# usb.net
KiCad netlist of a schematic drawn in EAGLE
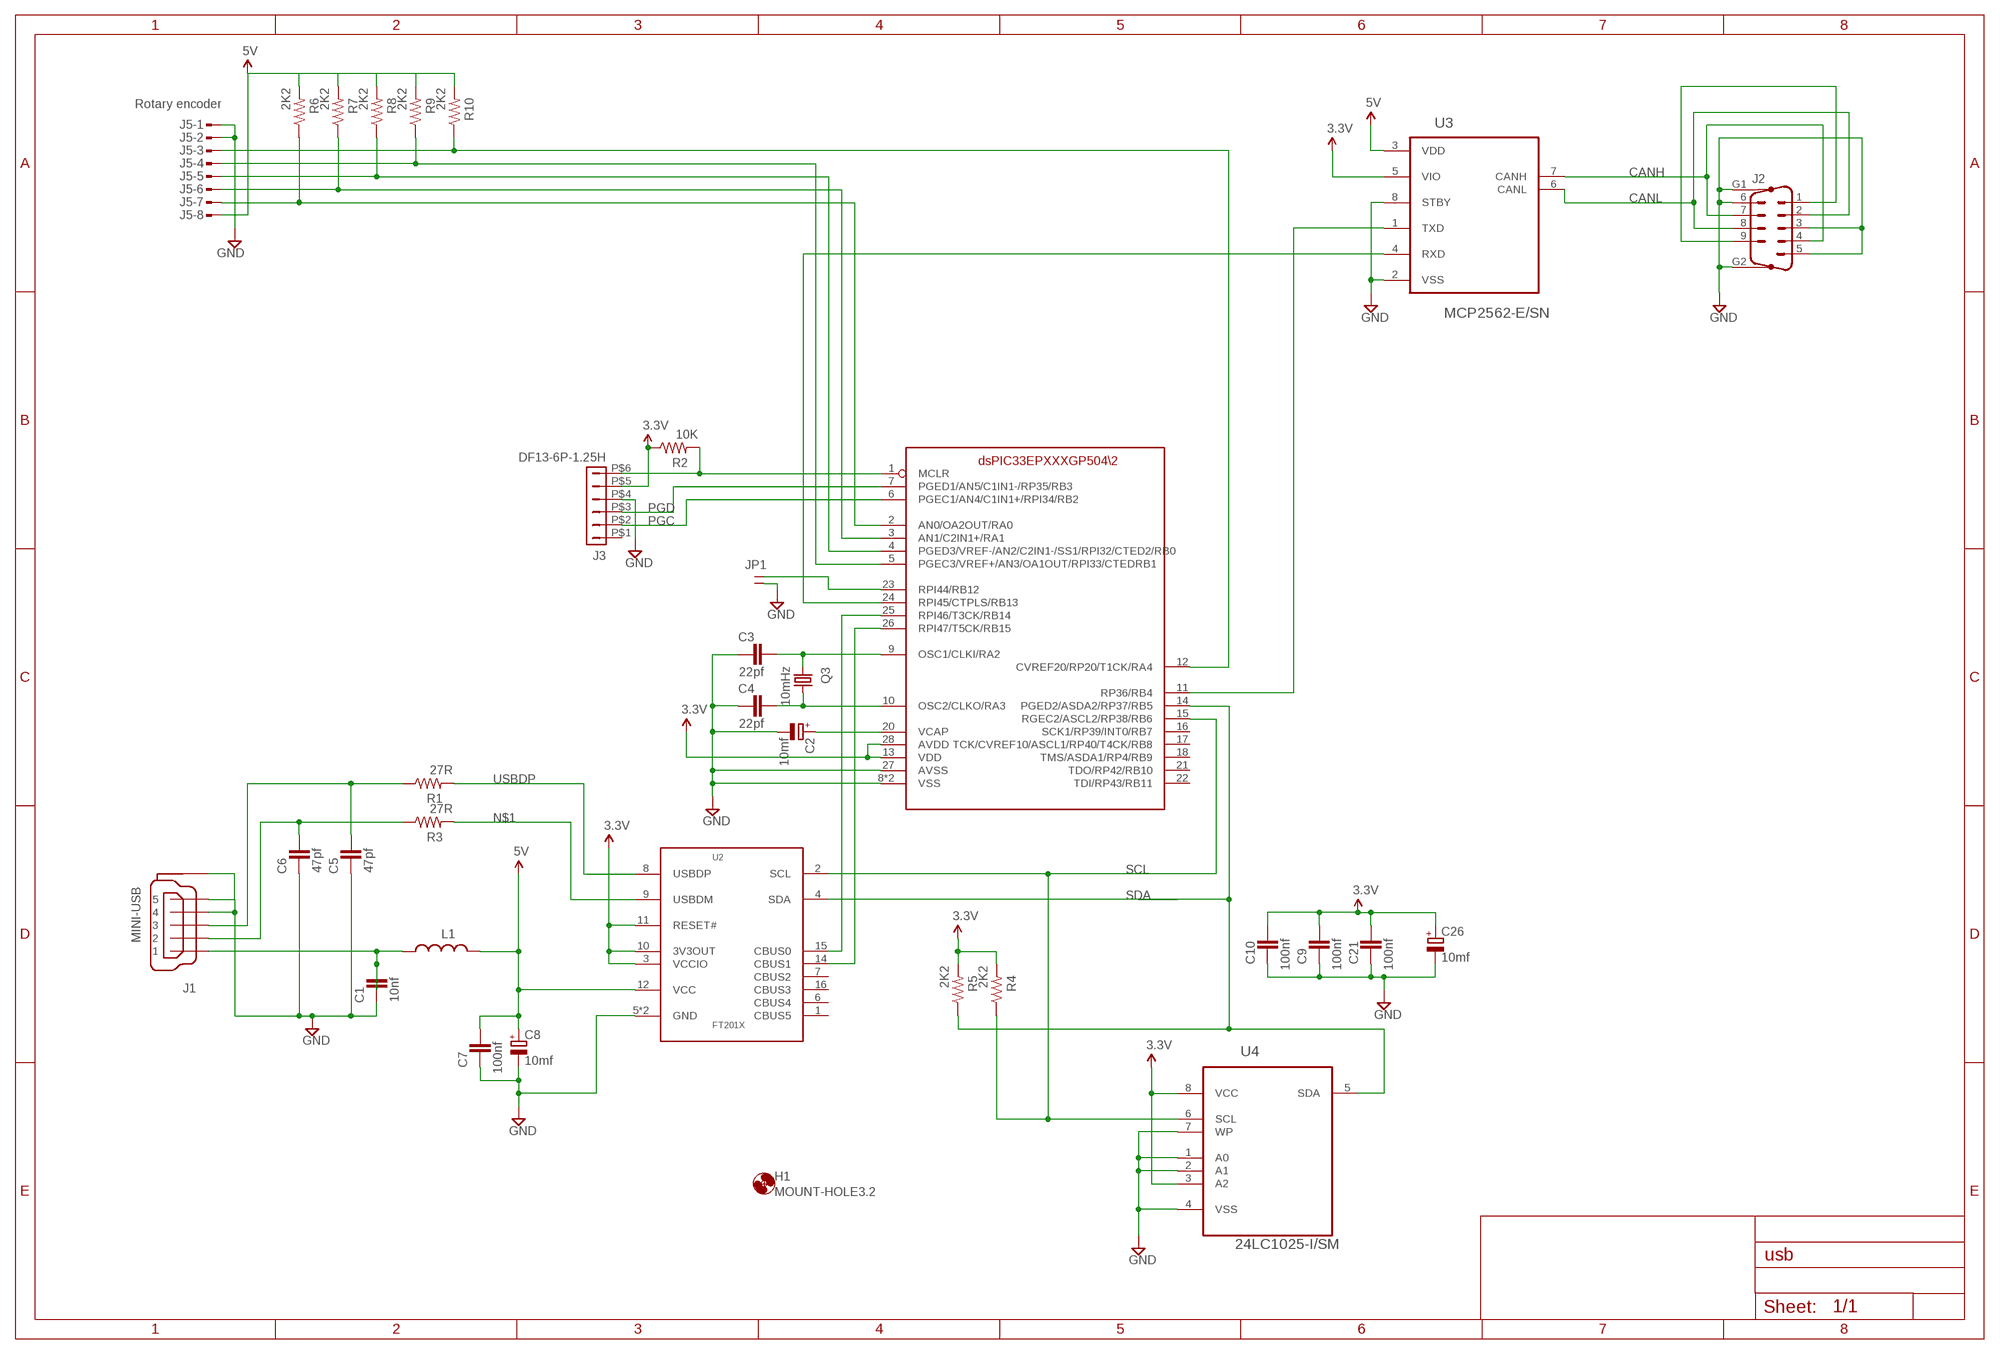
[diagram p0: schematic, sheet 1]

(export (version "E")
  (design (tool "Eeschema 10.0.6"))
  (components
    (comp (ref "C1")
      (value "10nf")
      (footprint "eagle-import:C805")
      (libsource (lib "eagle-import") (part "CAPACITOR_NPOL-0805"))
    )
    (comp (ref "C2")
      (value "10mf")
      (footprint "eagle-import:SMC_A")
      (libsource (lib "eagle-import") (part "CAPACITOR_POL-SMC_A"))
    )
    (comp (ref "C3")
      (value "22pf")
      (footprint "eagle-import:C805")
      (libsource (lib "eagle-import") (part "CAPACITOR_NPOL-0805"))
    )
    (comp (ref "C4")
      (value "22pf")
      (footprint "eagle-import:C805")
      (libsource (lib "eagle-import") (part "CAPACITOR_NPOL-0805"))
    )
    (comp (ref "C5")
      (value "47pf")
      (footprint "eagle-import:C805")
      (libsource (lib "eagle-import") (part "CAPACITOR_NPOL-0805"))
    )
    (comp (ref "C6")
      (value "47pf")
      (footprint "eagle-import:C805")
      (libsource (lib "eagle-import") (part "CAPACITOR_NPOL-0805"))
    )
    (comp (ref "C7")
      (value "100nf")
      (footprint "eagle-import:C805")
      (libsource (lib "eagle-import") (part "CAPACITOR_NPOL-0805"))
    )
    (comp (ref "C8")
      (value "10mf")
      (footprint "eagle-import:SMC_A")
      (libsource (lib "eagle-import") (part "CAPACITOR_POL-SMC_A"))
    )
    (comp (ref "C9")
      (value "100nf")
      (footprint "eagle-import:C805")
      (libsource (lib "eagle-import") (part "CAPACITOR_NPOL-0805"))
    )
    (comp (ref "C10")
      (value "100nf")
      (footprint "eagle-import:C805")
      (libsource (lib "eagle-import") (part "CAPACITOR_NPOL-0805"))
    )
    (comp (ref "C21")
      (value "100nf")
      (footprint "eagle-import:C805")
      (libsource (lib "eagle-import") (part "CAPACITOR_NPOL-0805"))
    )
    (comp (ref "C26")
      (value "10mf")
      (footprint "eagle-import:SMC_A")
      (libsource (lib "eagle-import") (part "CAPACITOR_POL-SMC_A"))
    )
    (comp (ref "H1")
      (value "MOUNT-HOLE3.2")
      (footprint "eagle-import:3,2")
      (libsource (lib "eagle-import") (part "MOUNT-HOLE3.2"))
    )
    (comp (ref "J1")
      (value "MINI-USB")
      (footprint "eagle-import:MINI-USB")
      (libsource (lib "eagle-import") (part "MINI-USB"))
    )
    (comp (ref "J2")
      (value "M09HP")
      (footprint "eagle-import:M09HP")
      (libsource (lib "eagle-import") (part "M09HP"))
    )
    (comp (ref "J3")
      (value "DF13-6P-1.25H")
      (footprint "eagle-import:DF13A-6P-1.25H")
      (libsource (lib "eagle-import") (part "DF13-6P-1.25H"))
    )
    (comp (ref "J5")
      (value "MTOP-8")
      (footprint "eagle-import:MTOP-8")
      (fields (field (name "PARTNO") "7-215079-8"))
      (libsource (lib "eagle-import") (part "MTOP-8"))
    )
    (comp (ref "JP1")
      (value "JUMPER-1X2")
      (footprint "eagle-import:JUMPER-1X2")
      (libsource (lib "eagle-import") (part "JUMPER-1X2"))
    )
    (comp (ref "L1")
      (value "FERRITE-0603")
      (footprint "eagle-import:FB603")
      (libsource (lib "eagle-import") (part "FERRITE-0603"))
    )
    (comp (ref "Q3")
      (value "10mHz")
      (footprint "eagle-import:HC49_S")
      (fields (field (name "PARTNO") "9B-10.000MBBK-B"))
      (libsource (lib "eagle-import") (part "CRYSTALHC49S"))
    )
    (comp (ref "R1")
      (value "27R")
      (footprint "eagle-import:0603-RES")
      (fields (field (name "PARTNO") "ERJ-3GEYJ103V"))
      (libsource (lib "eagle-import") (part "RESISTOR0603-RES"))
    )
    (comp (ref "R2")
      (value "10K")
      (footprint "eagle-import:0603-RES")
      (fields (field (name "PARTNO") "ERJ-3GEYJ103V"))
      (libsource (lib "eagle-import") (part "RESISTOR0603-RES"))
    )
    (comp (ref "R3")
      (value "27R")
      (footprint "eagle-import:0603-RES")
      (fields (field (name "PARTNO") "ERJ-3GEYJ103V"))
      (libsource (lib "eagle-import") (part "RESISTOR0603-RES"))
    )
    (comp (ref "R4")
      (value "2K2")
      (footprint "eagle-import:0603-RES")
      (fields (field (name "PARTNO") "ERJ-3GEYJ103V"))
      (libsource (lib "eagle-import") (part "RESISTOR0603-RES"))
    )
    (comp (ref "R5")
      (value "2K2")
      (footprint "eagle-import:0603-RES")
      (fields (field (name "PARTNO") "ERJ-3GEYJ103V"))
      (libsource (lib "eagle-import") (part "RESISTOR0603-RES"))
    )
    (comp (ref "R6")
      (value "2K2")
      (footprint "eagle-import:0603-RES")
      (fields (field (name "PARTNO") "RC0603FR-072K2L"))
      (libsource (lib "eagle-import") (part "RESISTOR0603-RES"))
    )
    (comp (ref "R7")
      (value "2K2")
      (footprint "eagle-import:0603-RES")
      (fields (field (name "PARTNO") "RC0603FR-072K2L"))
      (libsource (lib "eagle-import") (part "RESISTOR0603-RES"))
    )
    (comp (ref "R8")
      (value "2K2")
      (footprint "eagle-import:0603-RES")
      (fields (field (name "PARTNO") "RC0603FR-072K2L"))
      (libsource (lib "eagle-import") (part "RESISTOR0603-RES"))
    )
    (comp (ref "R9")
      (value "2K2")
      (footprint "eagle-import:0603-RES")
      (fields (field (name "PARTNO") "RC0603FR-072K2L"))
      (libsource (lib "eagle-import") (part "RESISTOR0603-RES"))
    )
    (comp (ref "R10")
      (value "2K2")
      (footprint "eagle-import:0603-RES")
      (fields (field (name "PARTNO") "RC0603FR-072K2L"))
      (libsource (lib "eagle-import") (part "RESISTOR0603-RES"))
    )
    (comp (ref "U1")
      (value "DSPIC33EPXXXGP502")
      (footprint "eagle-import:SOIC-28")
      (libsource (lib "eagle-import") (part "DSPIC33EPXXXGP502"))
    )
    (comp (ref "U2")
      (value "FT201X")
      (footprint "eagle-import:TSSOP-16")
      (libsource (lib "eagle-import") (part "FT201X"))
    )
    (comp (ref "U3")
      (value "MCP2562-E/SN")
      (footprint "eagle-import:SOIC-8N")
      (libsource (lib "eagle-import") (part "MCP2562-E/SN"))
    )
    (comp (ref "U4")
      (value "24LC1025-I/SM")
      (footprint "eagle-import:SOIC8-N_MC")
      (libsource (lib "eagle-import") (part "24LC1025-I/SM"))
    )
  )
  (nets
    (net (code "1") (name "/CANH") (class "Default")
      (node (ref "J2") (pin "4") (pinfunction "4_4") (pintype "passive"))
      (node (ref "J2") (pin "7") (pinfunction "7_7") (pintype "passive"))
      (node (ref "U3") (pin "7") (pinfunction "CANH_7") (pintype "bidirectional"))
    )
    (net (code "2") (name "/CANL") (class "Default")
      (node (ref "J2") (pin "2") (pinfunction "2_2") (pintype "passive"))
      (node (ref "J2") (pin "8") (pinfunction "8_8") (pintype "passive"))
      (node (ref "U3") (pin "6") (pinfunction "CANL_6") (pintype "bidirectional"))
    )
    (net (code "3") (name "/N$1") (class "Default")
      (node (ref "R3") (pin "2") (pinfunction "2_2") (pintype "passive"))
      (node (ref "U2") (pin "9") (pinfunction "USBDM_9") (pintype "bidirectional"))
    )
    (net (code "4") (name "/PGC") (class "Default")
      (node (ref "J3") (pin "P$2") (pinfunction "2_P$2") (pintype "passive"))
      (node (ref "U1") (pin "6") (pinfunction "PGEC1/AN4/C1IN1+/RPI34/RB2_6") (pintype "bidirectional"))
    )
    (net (code "5") (name "/PGD") (class "Default")
      (node (ref "J3") (pin "P$3") (pinfunction "3_P$3") (pintype "passive"))
      (node (ref "U1") (pin "7") (pinfunction "PGED1/AN5/C1IN1-/RP35/RB3_7") (pintype "bidirectional"))
    )
    (net (code "6") (name "/SCL") (class "Default")
      (node (ref "R4") (pin "1") (pinfunction "1_1") (pintype "passive"))
      (node (ref "U1") (pin "15") (pinfunction "RGEC2/ASCL2/RP38/RB6_15") (pintype "bidirectional"))
      (node (ref "U2") (pin "2") (pinfunction "SCL_2") (pintype "bidirectional"))
      (node (ref "U4") (pin "6") (pinfunction "SCL_6") (pintype "input"))
    )
    (net (code "7") (name "/SDA") (class "Default")
      (node (ref "R5") (pin "1") (pinfunction "1_1") (pintype "passive"))
      (node (ref "U1") (pin "14") (pinfunction "PGED2/ASDA2/RP37/RB5_14") (pintype "bidirectional"))
      (node (ref "U2") (pin "4") (pinfunction "SDA_4") (pintype "bidirectional"))
      (node (ref "U4") (pin "5") (pinfunction "SDA_5") (pintype "bidirectional"))
    )
    (net (code "8") (name "/USBDP") (class "Default")
      (node (ref "R1") (pin "2") (pinfunction "2_2") (pintype "passive"))
      (node (ref "U2") (pin "8") (pinfunction "USBDP_8") (pintype "bidirectional"))
    )
    (net (code "9") (name "3.3V") (class "Default")
      (node (ref "C10") (pin "1") (pinfunction "1_1") (pintype "passive"))
      (node (ref "C21") (pin "1") (pinfunction "1_1") (pintype "passive"))
      (node (ref "C26") (pin "+") (pinfunction "+_+") (pintype "passive"))
      (node (ref "C9") (pin "1") (pinfunction "1_1") (pintype "passive"))
      (node (ref "J3") (pin "P$5") (pinfunction "5_P$5") (pintype "passive"))
      (node (ref "R2") (pin "1") (pinfunction "1_1") (pintype "passive"))
      (node (ref "R4") (pin "2") (pinfunction "2_2") (pintype "passive"))
      (node (ref "R5") (pin "2") (pinfunction "2_2") (pintype "passive"))
      (node (ref "U1") (pin "13") (pinfunction "VDD_13") (pintype "bidirectional"))
      (node (ref "U1") (pin "28") (pinfunction "AVDD_28") (pintype "bidirectional"))
      (node (ref "U2") (pin "10") (pinfunction "3V3OUT_10") (pintype "bidirectional"))
      (node (ref "U2") (pin "11") (pinfunction "RESET#_11") (pintype "bidirectional"))
      (node (ref "U2") (pin "3") (pinfunction "VCCIO_3") (pintype "bidirectional"))
      (node (ref "U3") (pin "5") (pinfunction "VIO_5") (pintype "power_in"))
      (node (ref "U4") (pin "3") (pinfunction "A2_3") (pintype "input"))
      (node (ref "U4") (pin "8") (pinfunction "VCC_8") (pintype "power_in"))
    )
    (net (code "10") (name "5V") (class "Default")
      (node (ref "C7") (pin "1") (pinfunction "1_1") (pintype "passive"))
      (node (ref "C8") (pin "+") (pinfunction "+_+") (pintype "passive"))
      (node (ref "J5") (pin "8") (pinfunction "1_8") (pintype "passive"))
      (node (ref "L1") (pin "2") (pinfunction "2_2") (pintype "passive"))
      (node (ref "R10") (pin "2") (pinfunction "2_2") (pintype "passive"))
      (node (ref "R6") (pin "2") (pinfunction "2_2") (pintype "passive"))
      (node (ref "R7") (pin "2") (pinfunction "2_2") (pintype "passive"))
      (node (ref "R8") (pin "2") (pinfunction "2_2") (pintype "passive"))
      (node (ref "R9") (pin "2") (pinfunction "2_2") (pintype "passive"))
      (node (ref "U2") (pin "12") (pinfunction "VCC_12") (pintype "bidirectional"))
      (node (ref "U3") (pin "3") (pinfunction "VDD_3") (pintype "power_in"))
    )
    (net (code "11") (name "GND") (class "Default")
      (node (ref "C1") (pin "2") (pinfunction "2_2") (pintype "passive"))
      (node (ref "C10") (pin "2") (pinfunction "2_2") (pintype "passive"))
      (node (ref "C2") (pin "-") (pinfunction "-_-") (pintype "passive"))
      (node (ref "C21") (pin "2") (pinfunction "2_2") (pintype "passive"))
      (node (ref "C26") (pin "-") (pinfunction "-_-") (pintype "passive"))
      (node (ref "C3") (pin "2") (pinfunction "2_2") (pintype "passive"))
      (node (ref "C4") (pin "2") (pinfunction "2_2") (pintype "passive"))
      (node (ref "C5") (pin "2") (pinfunction "2_2") (pintype "passive"))
      (node (ref "C6") (pin "2") (pinfunction "2_2") (pintype "passive"))
      (node (ref "C7") (pin "2") (pinfunction "2_2") (pintype "passive"))
      (node (ref "C8") (pin "-") (pinfunction "-_-") (pintype "passive"))
      (node (ref "C9") (pin "2") (pinfunction "2_2") (pintype "passive"))
      (node (ref "J1") (pin "4") (pinfunction "4_4") (pintype "input"))
      (node (ref "J1") (pin "5") (pinfunction "5_5") (pintype "input"))
      (node (ref "J1") (pin "M1") (pinfunction "MOUNT_M1") (pintype "bidirectional"))
      (node (ref "J1") (pin "M2") (pinfunction "MOUNT_M2") (pintype "bidirectional"))
      (node (ref "J1") (pin "M3") (pinfunction "MOUNT_M3") (pintype "bidirectional"))
      (node (ref "J1") (pin "M4") (pinfunction "MOUNT_M4") (pintype "bidirectional"))
      (node (ref "J2") (pin "3") (pinfunction "3_3") (pintype "passive"))
      (node (ref "J2") (pin "5") (pinfunction "5_5") (pintype "passive"))
      (node (ref "J2") (pin "6") (pinfunction "6_6") (pintype "passive"))
      (node (ref "J2") (pin "G1") (pinfunction "G1_G1") (pintype "passive"))
      (node (ref "J2") (pin "G2") (pinfunction "G2_G2") (pintype "passive"))
      (node (ref "J3") (pin "P$4") (pinfunction "4_P$4") (pintype "passive"))
      (node (ref "J5") (pin "1") (pinfunction "1_1") (pintype "passive"))
      (node (ref "J5") (pin "2") (pinfunction "1_2") (pintype "passive"))
      (node (ref "JP1") (pin "2") (pinfunction "2_2") (pintype "bidirectional"))
      (node (ref "U1") (pin "19") (pinfunction "VSS_19") (pintype "bidirectional"))
      (node (ref "U1") (pin "27") (pinfunction "AVSS_27") (pintype "bidirectional"))
      (node (ref "U1") (pin "8") (pinfunction "VSS_8") (pintype "bidirectional"))
      (node (ref "U2") (pin "13") (pinfunction "GND_13") (pintype "power_in"))
      (node (ref "U2") (pin "5") (pinfunction "GND_5") (pintype "power_in"))
      (node (ref "U3") (pin "2") (pinfunction "VSS_2") (pintype "power_in"))
      (node (ref "U3") (pin "8") (pinfunction "STBY_8") (pintype "input"))
      (node (ref "U4") (pin "1") (pinfunction "A0_1") (pintype "input"))
      (node (ref "U4") (pin "2") (pinfunction "A1_2") (pintype "input"))
      (node (ref "U4") (pin "4") (pinfunction "VSS_4") (pintype "passive"))
      (node (ref "U4") (pin "7") (pinfunction "WP_7") (pintype "input"))
    )
    (net (code "12") (name "Net-(C1-Pad1)") (class "Default")
      (node (ref "C1") (pin "1") (pinfunction "1_1") (pintype "passive"))
      (node (ref "J1") (pin "1") (pinfunction "1_1") (pintype "input"))
      (node (ref "L1") (pin "1") (pinfunction "1_1") (pintype "passive"))
    )
    (net (code "13") (name "Net-(C5-Pad1)") (class "Default")
      (node (ref "C5") (pin "1") (pinfunction "1_1") (pintype "passive"))
      (node (ref "J1") (pin "3") (pinfunction "3_3") (pintype "input"))
      (node (ref "R1") (pin "1") (pinfunction "1_1") (pintype "passive"))
    )
    (net (code "14") (name "Net-(C6-Pad1)") (class "Default")
      (node (ref "C6") (pin "1") (pinfunction "1_1") (pintype "passive"))
      (node (ref "J1") (pin "2") (pinfunction "2_2") (pintype "input"))
      (node (ref "R3") (pin "1") (pinfunction "1_1") (pintype "passive"))
    )
    (net (code "15") (name "Net-(J2-Pad1)") (class "Default")
      (node (ref "J2") (pin "1") (pinfunction "1_1") (pintype "passive"))
      (node (ref "J2") (pin "9") (pinfunction "9_9") (pintype "passive"))
    )
    (net (code "16") (name "Net-(J3-6)") (class "Default")
      (node (ref "J3") (pin "P$6") (pinfunction "6_P$6") (pintype "passive"))
      (node (ref "R2") (pin "2") (pinfunction "2_2") (pintype "passive"))
      (node (ref "U1") (pin "1") (pinfunction "MCLR_1") (pintype "input"))
    )
    (net (code "17") (name "Net-(J5C-1)") (class "Default")
      (node (ref "J5") (pin "3") (pinfunction "1_3") (pintype "passive"))
      (node (ref "R10") (pin "1") (pinfunction "1_1") (pintype "passive"))
      (node (ref "U1") (pin "12") (pinfunction "CVREF20/RP20/T1CK/RA4_12") (pintype "bidirectional"))
    )
    (net (code "18") (name "Net-(J5D-1)") (class "Default")
      (node (ref "J5") (pin "4") (pinfunction "1_4") (pintype "passive"))
      (node (ref "R9") (pin "1") (pinfunction "1_1") (pintype "passive"))
      (node (ref "U1") (pin "5") (pinfunction "PGEC3/VREF+/AN3/OA1OUT/RPI33/CTEDRB1_5") (pintype "bidirectional"))
    )
    (net (code "19") (name "Net-(J5E-1)") (class "Default")
      (node (ref "J5") (pin "5") (pinfunction "1_5") (pintype "passive"))
      (node (ref "R8") (pin "1") (pinfunction "1_1") (pintype "passive"))
      (node (ref "U1") (pin "4") (pinfunction "PGED3/VREF-/AN2/C2IN1-/SS1/RPI32/CTED2/RB0_4") (pintype "bidirectional"))
    )
    (net (code "20") (name "Net-(J5F-1)") (class "Default")
      (node (ref "J5") (pin "6") (pinfunction "1_6") (pintype "passive"))
      (node (ref "R7") (pin "1") (pinfunction "1_1") (pintype "passive"))
      (node (ref "U1") (pin "3") (pinfunction "AN1/C2IN1+/RA1_3") (pintype "bidirectional"))
    )
    (net (code "21") (name "Net-(J5G-1)") (class "Default")
      (node (ref "J5") (pin "7") (pinfunction "1_7") (pintype "passive"))
      (node (ref "R6") (pin "1") (pinfunction "1_1") (pintype "passive"))
      (node (ref "U1") (pin "2") (pinfunction "AN0/OA2OUT/RA0_2") (pintype "bidirectional"))
    )
    (net (code "22") (name "Net-(U1-OSC1{slash}CLKI{slash}RA2)") (class "Default")
      (node (ref "C3") (pin "1") (pinfunction "1_1") (pintype "passive"))
      (node (ref "Q3") (pin "2") (pinfunction "2_2") (pintype "passive"))
      (node (ref "U1") (pin "9") (pinfunction "OSC1/CLKI/RA2_9") (pintype "bidirectional"))
    )
    (net (code "23") (name "Net-(U1-OSC2{slash}CLKO{slash}RA3)") (class "Default")
      (node (ref "C4") (pin "1") (pinfunction "1_1") (pintype "passive"))
      (node (ref "Q3") (pin "1") (pinfunction "1_1") (pintype "passive"))
      (node (ref "U1") (pin "10") (pinfunction "OSC2/CLKO/RA3_10") (pintype "bidirectional"))
    )
    (net (code "24") (name "Net-(U1-RP36{slash}RB4)") (class "Default")
      (node (ref "U1") (pin "11") (pinfunction "RP36/RB4_11") (pintype "bidirectional"))
      (node (ref "U3") (pin "1") (pinfunction "TXD_1") (pintype "input"))
    )
    (net (code "25") (name "Net-(U1-RPI44{slash}RB12)") (class "Default")
      (node (ref "JP1") (pin "1") (pinfunction "1_1") (pintype "bidirectional"))
      (node (ref "U1") (pin "23") (pinfunction "RPI44/RB12_23") (pintype "bidirectional"))
    )
    (net (code "26") (name "Net-(U1-RPI45{slash}CTPLS{slash}RB13)") (class "Default")
      (node (ref "U1") (pin "24") (pinfunction "RPI45/CTPLS/RB13_24") (pintype "bidirectional"))
      (node (ref "U3") (pin "4") (pinfunction "RXD_4") (pintype "output"))
    )
    (net (code "27") (name "Net-(U1-RPI46{slash}T3CK{slash}RB14)") (class "Default")
      (node (ref "U1") (pin "25") (pinfunction "RPI46/T3CK/RB14_25") (pintype "bidirectional"))
      (node (ref "U2") (pin "15") (pinfunction "CBUS0_15") (pintype "bidirectional"))
    )
    (net (code "28") (name "Net-(U1-RPI47{slash}T5CK{slash}RB15)") (class "Default")
      (node (ref "U1") (pin "26") (pinfunction "RPI47/T5CK/RB15_26") (pintype "bidirectional"))
      (node (ref "U2") (pin "14") (pinfunction "CBUS1_14") (pintype "bidirectional"))
    )
    (net (code "29") (name "Net-(U1-VCAP)") (class "Default")
      (node (ref "C2") (pin "+") (pinfunction "+_+") (pintype "passive"))
      (node (ref "U1") (pin "20") (pinfunction "VCAP_20") (pintype "bidirectional"))
    )
    (net (code "30") (name "unconnected-(J3-1-PadP$1)") (class "Default")
      (node (ref "J3") (pin "P$1") (pinfunction "1_P$1") (pintype "passive"))
    )
    (net (code "31") (name "unconnected-(U1-SCK1{slash}RP39{slash}INT0{slash}RB7-Pad16)") (class "Default")
      (node (ref "U1") (pin "16") (pinfunction "SCK1/RP39/INT0/RB7_16") (pintype "bidirectional"))
    )
    (net (code "32") (name "unconnected-(U1-TCK{slash}CVREF10{slash}ASCL1{slash}RP40{slash}T4CK{slash}RB8-Pad17)") (class "Default")
      (node (ref "U1") (pin "17") (pinfunction "TCK/CVREF10/ASCL1/RP40/T4CK/RB8_17") (pintype "bidirectional"))
    )
    (net (code "33") (name "unconnected-(U1-TDI{slash}RP43{slash}RB11-Pad22)") (class "Default")
      (node (ref "U1") (pin "22") (pinfunction "TDI/RP43/RB11_22") (pintype "bidirectional"))
    )
    (net (code "34") (name "unconnected-(U1-TDO{slash}RP42{slash}RB10-Pad21)") (class "Default")
      (node (ref "U1") (pin "21") (pinfunction "TDO/RP42/RB10_21") (pintype "bidirectional"))
    )
    (net (code "35") (name "unconnected-(U1-TMS{slash}ASDA1{slash}RP4{slash}RB9-Pad18)") (class "Default")
      (node (ref "U1") (pin "18") (pinfunction "TMS/ASDA1/RP4/RB9_18") (pintype "bidirectional"))
    )
    (net (code "36") (name "unconnected-(U2-CBUS2-Pad7)") (class "Default")
      (node (ref "U2") (pin "7") (pinfunction "CBUS2_7") (pintype "bidirectional"))
    )
    (net (code "37") (name "unconnected-(U2-CBUS3-Pad16)") (class "Default")
      (node (ref "U2") (pin "16") (pinfunction "CBUS3_16") (pintype "bidirectional"))
    )
    (net (code "38") (name "unconnected-(U2-CBUS4-Pad6)") (class "Default")
      (node (ref "U2") (pin "6") (pinfunction "CBUS4_6") (pintype "bidirectional"))
    )
    (net (code "39") (name "unconnected-(U2-CBUS5-Pad1)") (class "Default")
      (node (ref "U2") (pin "1") (pinfunction "CBUS5_1") (pintype "bidirectional"))
    )
  )
)
